# design.net
KiCad netlist of a schematic drawn in Altium Designer
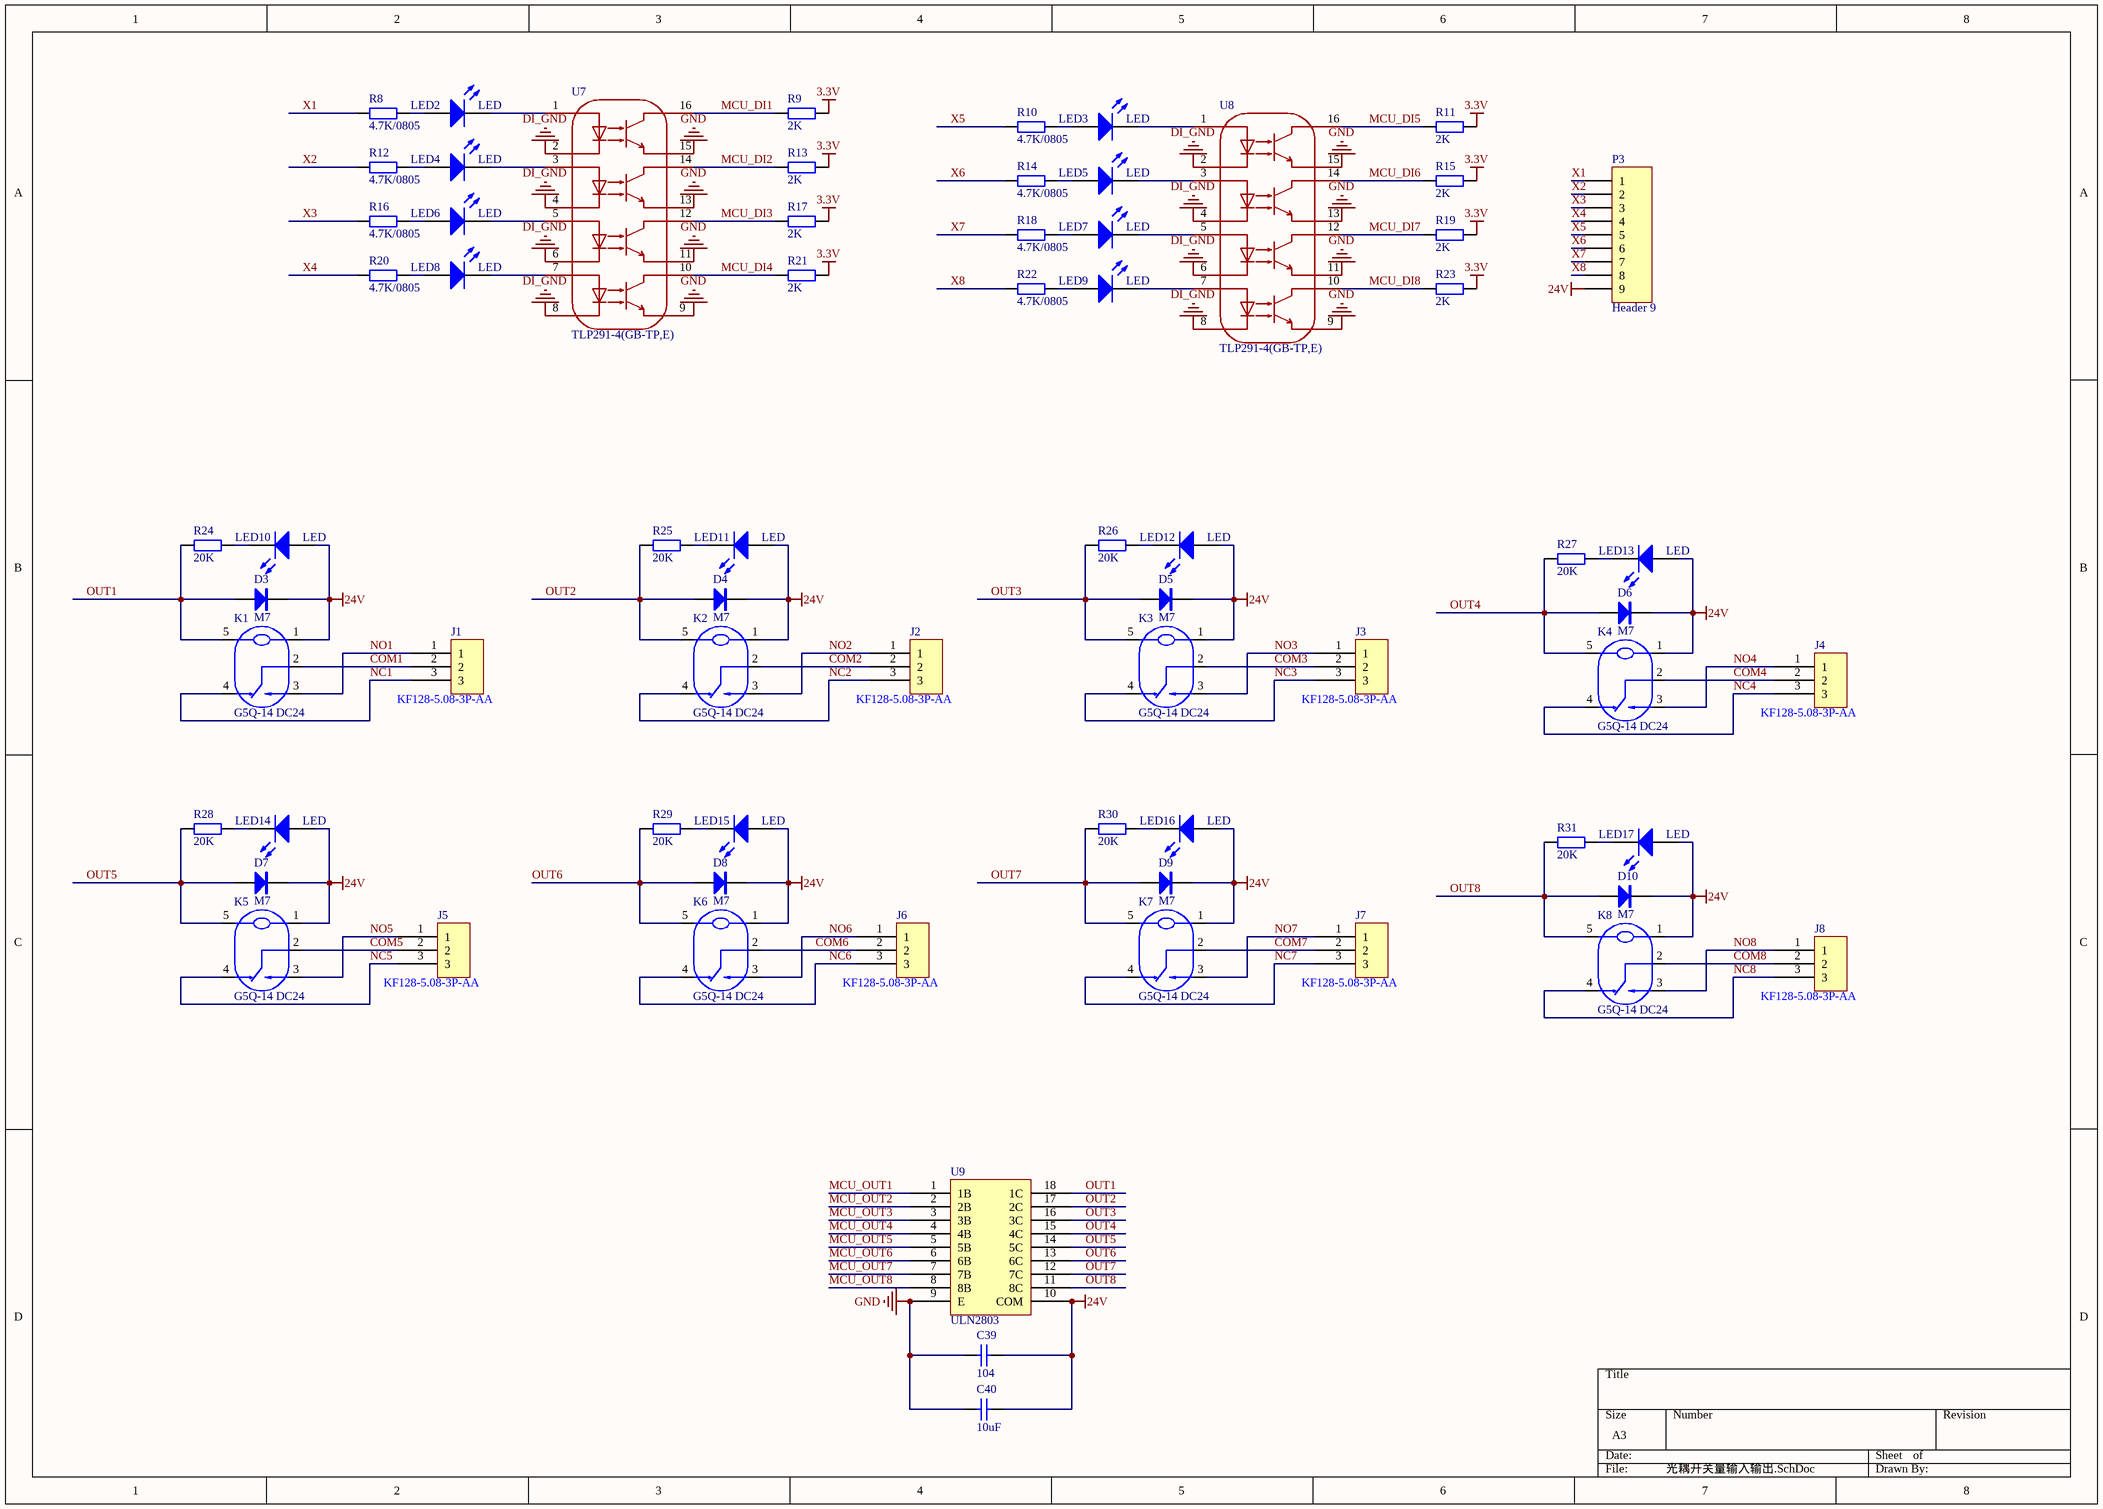
[diagram p0: 光耦开关量输入输出.SchDoc]

(export (version "E")
  (design (tool "Eeschema 10.0.6"))
  (components
    (comp (ref "C39")
      (value "104")
      (footprint "C 0603_L")
      (description "0603贴片电容")
      (fields (field (name "PUBLISHER") "Altium Limited"))
      (libsource (lib "STM32_PLC_20251215") (part "Cap"))
    )
    (comp (ref "C40")
      (value "10uF")
      (footprint "C 0603_L")
      (description "0603贴片电容")
      (fields (field (name "PUBLISHER") "Altium Limited"))
      (libsource (lib "STM32_PLC_20251215") (part "Cap"))
    )
    (comp (ref "D3")
      (value "M7")
      (footprint "SMA")
      (description "整流二极管")
      (libsource (lib "STM32_PLC_20251215") (part "M7"))
    )
    (comp (ref "D4")
      (value "M7")
      (footprint "SMA")
      (description "整流二极管")
      (libsource (lib "STM32_PLC_20251215") (part "M7"))
    )
    (comp (ref "D5")
      (value "M7")
      (footprint "SMA")
      (description "整流二极管")
      (libsource (lib "STM32_PLC_20251215") (part "M7"))
    )
    (comp (ref "D6")
      (value "M7")
      (footprint "SMA")
      (description "整流二极管")
      (libsource (lib "STM32_PLC_20251215") (part "M7"))
    )
    (comp (ref "D7")
      (value "M7")
      (footprint "SMA")
      (description "整流二极管")
      (libsource (lib "STM32_PLC_20251215") (part "M7"))
    )
    (comp (ref "D8")
      (value "M7")
      (footprint "SMA")
      (description "整流二极管")
      (libsource (lib "STM32_PLC_20251215") (part "M7"))
    )
    (comp (ref "D9")
      (value "M7")
      (footprint "SMA")
      (description "整流二极管")
      (libsource (lib "STM32_PLC_20251215") (part "M7"))
    )
    (comp (ref "D10")
      (value "M7")
      (footprint "SMA")
      (description "整流二极管")
      (libsource (lib "STM32_PLC_20251215") (part "M7"))
    )
    (comp (ref "J1")
      (value "KF128-5.08-3P-AA")
      (footprint "KF128-5.08-3P")
      (description "KF128-5.08-3P-AA端座")
      (fields (field (name "MANUFACTURER") "KEFA(科发)"))
      (libsource (lib "STM32_PLC_20251215") (part "KF128-5.08-3P-AA"))
    )
    (comp (ref "J2")
      (value "KF128-5.08-3P-AA")
      (footprint "KF128-5.08-3P")
      (description "KF128-5.08-3P-AA端座")
      (fields (field (name "MANUFACTURER") "KEFA(科发)"))
      (libsource (lib "STM32_PLC_20251215") (part "KF128-5.08-3P-AA"))
    )
    (comp (ref "J3")
      (value "KF128-5.08-3P-AA")
      (footprint "KF128-5.08-3P")
      (description "KF128-5.08-3P-AA端座")
      (fields (field (name "MANUFACTURER") "KEFA(科发)"))
      (libsource (lib "STM32_PLC_20251215") (part "KF128-5.08-3P-AA"))
    )
    (comp (ref "J4")
      (value "KF128-5.08-3P-AA")
      (footprint "KF128-5.08-3P")
      (description "KF128-5.08-3P-AA端座")
      (fields (field (name "MANUFACTURER") "KEFA(科发)"))
      (libsource (lib "STM32_PLC_20251215") (part "KF128-5.08-3P-AA"))
    )
    (comp (ref "J5")
      (value "KF128-5.08-3P-AA")
      (footprint "KF128-5.08-3P")
      (description "KF128-5.08-3P-AA端座")
      (fields (field (name "MANUFACTURER") "KEFA(科发)"))
      (libsource (lib "STM32_PLC_20251215") (part "KF128-5.08-3P-AA"))
    )
    (comp (ref "J6")
      (value "KF128-5.08-3P-AA")
      (footprint "KF128-5.08-3P")
      (description "KF128-5.08-3P-AA端座")
      (fields (field (name "MANUFACTURER") "KEFA(科发)"))
      (libsource (lib "STM32_PLC_20251215") (part "KF128-5.08-3P-AA"))
    )
    (comp (ref "J7")
      (value "KF128-5.08-3P-AA")
      (footprint "KF128-5.08-3P")
      (description "KF128-5.08-3P-AA端座")
      (fields (field (name "MANUFACTURER") "KEFA(科发)"))
      (libsource (lib "STM32_PLC_20251215") (part "KF128-5.08-3P-AA"))
    )
    (comp (ref "J8")
      (value "KF128-5.08-3P-AA")
      (footprint "KF128-5.08-3P")
      (description "KF128-5.08-3P-AA端座")
      (fields (field (name "MANUFACTURER") "KEFA(科发)"))
      (libsource (lib "STM32_PLC_20251215") (part "KF128-5.08-3P-AA"))
    )
    (comp (ref "K1")
      (value "G5Q-14 DC24")
      (footprint "RELAY-TH_G5Q-14-DCXX")
      (description "欧姆龙24V继电器，单刀双掷")
      (fields (field (name "MANUFACTURER") "OMRON(欧姆龙)"))
      (libsource (lib "STM32F407_PLC_20260104_") (part "G5Q-14 DC24"))
    )
    (comp (ref "K2")
      (value "G5Q-14 DC24")
      (footprint "RELAY-TH_G5Q-14-DCXX")
      (description "欧姆龙24V继电器，单刀双掷")
      (fields (field (name "MANUFACTURER") "OMRON(欧姆龙)"))
      (libsource (lib "STM32F407_PLC_20260104_") (part "G5Q-14 DC24"))
    )
    (comp (ref "K3")
      (value "G5Q-14 DC24")
      (footprint "RELAY-TH_G5Q-14-DCXX")
      (description "欧姆龙24V继电器，单刀双掷")
      (fields (field (name "MANUFACTURER") "OMRON(欧姆龙)"))
      (libsource (lib "STM32F407_PLC_20260104_") (part "G5Q-14 DC24"))
    )
    (comp (ref "K4")
      (value "G5Q-14 DC24")
      (footprint "RELAY-TH_G5Q-14-DCXX")
      (description "欧姆龙24V继电器，单刀双掷")
      (fields (field (name "MANUFACTURER") "OMRON(欧姆龙)"))
      (libsource (lib "STM32F407_PLC_20260104_") (part "G5Q-14 DC24"))
    )
    (comp (ref "K5")
      (value "G5Q-14 DC24")
      (footprint "RELAY-TH_G5Q-14-DCXX")
      (description "欧姆龙24V继电器，单刀双掷")
      (fields (field (name "MANUFACTURER") "OMRON(欧姆龙)"))
      (libsource (lib "STM32F407_PLC_20260104_") (part "G5Q-14 DC24"))
    )
    (comp (ref "K6")
      (value "G5Q-14 DC24")
      (footprint "RELAY-TH_G5Q-14-DCXX")
      (description "欧姆龙24V继电器，单刀双掷")
      (fields (field (name "MANUFACTURER") "OMRON(欧姆龙)"))
      (libsource (lib "STM32F407_PLC_20260104_") (part "G5Q-14 DC24"))
    )
    (comp (ref "K7")
      (value "G5Q-14 DC24")
      (footprint "RELAY-TH_G5Q-14-DCXX")
      (description "欧姆龙24V继电器，单刀双掷")
      (fields (field (name "MANUFACTURER") "OMRON(欧姆龙)"))
      (libsource (lib "STM32F407_PLC_20260104_") (part "G5Q-14 DC24"))
    )
    (comp (ref "K8")
      (value "G5Q-14 DC24")
      (footprint "RELAY-TH_G5Q-14-DCXX")
      (description "欧姆龙24V继电器，单刀双掷")
      (fields (field (name "MANUFACTURER") "OMRON(欧姆龙)"))
      (libsource (lib "STM32F407_PLC_20260104_") (part "G5Q-14 DC24"))
    )
    (comp (ref "LED2")
      (value "LED")
      (footprint "LED 0603R")
      (description "0603发光二极管")
      (fields (field (name "PUBLISHER") "Altium Limited"))
      (libsource (lib "STM32_PLC_20251215_1") (part "LED"))
    )
    (comp (ref "LED3")
      (value "LED")
      (footprint "LED 0603R")
      (description "0603发光二极管")
      (fields (field (name "PUBLISHER") "Altium Limited"))
      (libsource (lib "STM32_PLC_20251215_1") (part "LED"))
    )
    (comp (ref "LED4")
      (value "LED")
      (footprint "LED 0603R")
      (description "0603发光二极管")
      (fields (field (name "PUBLISHER") "Altium Limited"))
      (libsource (lib "STM32_PLC_20251215_1") (part "LED"))
    )
    (comp (ref "LED5")
      (value "LED")
      (footprint "LED 0603R")
      (description "0603发光二极管")
      (fields (field (name "PUBLISHER") "Altium Limited"))
      (libsource (lib "STM32_PLC_20251215_1") (part "LED"))
    )
    (comp (ref "LED6")
      (value "LED")
      (footprint "LED 0603R")
      (description "0603发光二极管")
      (fields (field (name "PUBLISHER") "Altium Limited"))
      (libsource (lib "STM32_PLC_20251215_1") (part "LED"))
    )
    (comp (ref "LED7")
      (value "LED")
      (footprint "LED 0603R")
      (description "0603发光二极管")
      (fields (field (name "PUBLISHER") "Altium Limited"))
      (libsource (lib "STM32_PLC_20251215_1") (part "LED"))
    )
    (comp (ref "LED8")
      (value "LED")
      (footprint "LED 0603R")
      (description "0603发光二极管")
      (fields (field (name "PUBLISHER") "Altium Limited"))
      (libsource (lib "STM32_PLC_20251215_1") (part "LED"))
    )
    (comp (ref "LED9")
      (value "LED")
      (footprint "LED 0603R")
      (description "0603发光二极管")
      (fields (field (name "PUBLISHER") "Altium Limited"))
      (libsource (lib "STM32_PLC_20251215_1") (part "LED"))
    )
    (comp (ref "LED10")
      (value "LED")
      (footprint "LED 0603R")
      (description "0603发光二极管")
      (fields (field (name "PUBLISHER") "Altium Limited"))
      (libsource (lib "STM32_PLC_20251215_1") (part "LED"))
    )
    (comp (ref "LED11")
      (value "LED")
      (footprint "LED 0603R")
      (description "0603发光二极管")
      (fields (field (name "PUBLISHER") "Altium Limited"))
      (libsource (lib "STM32_PLC_20251215_1") (part "LED"))
    )
    (comp (ref "LED12")
      (value "LED")
      (footprint "LED 0603R")
      (description "0603发光二极管")
      (fields (field (name "PUBLISHER") "Altium Limited"))
      (libsource (lib "STM32_PLC_20251215_1") (part "LED"))
    )
    (comp (ref "LED13")
      (value "LED")
      (footprint "LED 0603R")
      (description "0603发光二极管")
      (fields (field (name "PUBLISHER") "Altium Limited"))
      (libsource (lib "STM32_PLC_20251215_1") (part "LED"))
    )
    (comp (ref "LED14")
      (value "LED")
      (footprint "LED 0603R")
      (description "0603发光二极管")
      (fields (field (name "PUBLISHER") "Altium Limited"))
      (libsource (lib "STM32_PLC_20251215_1") (part "LED"))
    )
    (comp (ref "LED15")
      (value "LED")
      (footprint "LED 0603R")
      (description "0603发光二极管")
      (fields (field (name "PUBLISHER") "Altium Limited"))
      (libsource (lib "STM32_PLC_20251215_1") (part "LED"))
    )
    (comp (ref "LED16")
      (value "LED")
      (footprint "LED 0603R")
      (description "0603发光二极管")
      (fields (field (name "PUBLISHER") "Altium Limited"))
      (libsource (lib "STM32_PLC_20251215_1") (part "LED"))
    )
    (comp (ref "LED17")
      (value "LED")
      (footprint "LED 0603R")
      (description "0603发光二极管")
      (fields (field (name "PUBLISHER") "Altium Limited"))
      (libsource (lib "STM32_PLC_20251215_1") (part "LED"))
    )
    (comp (ref "P3")
      (value "Header 9")
      (footprint "KF128-5.08-9P")
      (description "Header, 9-Pin")
      (fields (field (name "PUBLISHER") "Altium Limited"))
      (libsource (lib "Miscellaneous Connectors") (part "Header 9"))
    )
    (comp (ref "R8")
      (value "4.7K/0805")
      (footprint "R0805_L")
      (description "R0805贴片电阻")
      (fields (field (name "版权归属") "源创客"))
      (libsource (lib "STM32_PLC_20251215_1") (part "Res_15"))
    )
    (comp (ref "R9")
      (value "2K")
      (footprint "R 0603_L")
      (description "0603贴片电阻")
      (fields (field (name "版权归属") "源创客"))
      (libsource (lib "STM32_PLC_20251215") (part "Res"))
    )
    (comp (ref "R10")
      (value "4.7K/0805")
      (footprint "R0805_L")
      (description "R0805贴片电阻")
      (fields (field (name "版权归属") "源创客"))
      (libsource (lib "STM32_PLC_20251215_1") (part "Res_15"))
    )
    (comp (ref "R11")
      (value "2K")
      (footprint "R 0603_L")
      (description "0603贴片电阻")
      (fields (field (name "版权归属") "源创客"))
      (libsource (lib "STM32_PLC_20251215") (part "Res"))
    )
    (comp (ref "R12")
      (value "4.7K/0805")
      (footprint "R0805_L")
      (description "R0805贴片电阻")
      (fields (field (name "版权归属") "源创客"))
      (libsource (lib "STM32_PLC_20251215_1") (part "Res_15"))
    )
    (comp (ref "R13")
      (value "2K")
      (footprint "R 0603_L")
      (description "0603贴片电阻")
      (fields (field (name "版权归属") "源创客"))
      (libsource (lib "STM32_PLC_20251215") (part "Res"))
    )
    (comp (ref "R14")
      (value "4.7K/0805")
      (footprint "R0805_L")
      (description "R0805贴片电阻")
      (fields (field (name "版权归属") "源创客"))
      (libsource (lib "STM32_PLC_20251215_1") (part "Res_15"))
    )
    (comp (ref "R15")
      (value "2K")
      (footprint "R 0603_L")
      (description "0603贴片电阻")
      (fields (field (name "版权归属") "源创客"))
      (libsource (lib "STM32_PLC_20251215") (part "Res"))
    )
    (comp (ref "R16")
      (value "4.7K/0805")
      (footprint "R0805_L")
      (description "R0805贴片电阻")
      (fields (field (name "版权归属") "源创客"))
      (libsource (lib "STM32_PLC_20251215_1") (part "Res_15"))
    )
    (comp (ref "R17")
      (value "2K")
      (footprint "R 0603_L")
      (description "0603贴片电阻")
      (fields (field (name "版权归属") "源创客"))
      (libsource (lib "STM32_PLC_20251215") (part "Res"))
    )
    (comp (ref "R18")
      (value "4.7K/0805")
      (footprint "R0805_L")
      (description "R0805贴片电阻")
      (fields (field (name "版权归属") "源创客"))
      (libsource (lib "STM32_PLC_20251215_1") (part "Res_15"))
    )
    (comp (ref "R19")
      (value "2K")
      (footprint "R 0603_L")
      (description "0603贴片电阻")
      (fields (field (name "版权归属") "源创客"))
      (libsource (lib "STM32_PLC_20251215") (part "Res"))
    )
    (comp (ref "R20")
      (value "4.7K/0805")
      (footprint "R0805_L")
      (description "R0805贴片电阻")
      (fields (field (name "版权归属") "源创客"))
      (libsource (lib "STM32_PLC_20251215_1") (part "Res_15"))
    )
    (comp (ref "R21")
      (value "2K")
      (footprint "R 0603_L")
      (description "0603贴片电阻")
      (fields (field (name "版权归属") "源创客"))
      (libsource (lib "STM32_PLC_20251215") (part "Res"))
    )
    (comp (ref "R22")
      (value "4.7K/0805")
      (footprint "R0805_L")
      (description "R0805贴片电阻")
      (fields (field (name "版权归属") "源创客"))
      (libsource (lib "STM32_PLC_20251215_1") (part "Res_15"))
    )
    (comp (ref "R23")
      (value "2K")
      (footprint "R 0603_L")
      (description "0603贴片电阻")
      (fields (field (name "版权归属") "源创客"))
      (libsource (lib "STM32_PLC_20251215") (part "Res"))
    )
    (comp (ref "R24")
      (value "20K")
      (footprint "R 0603_L")
      (description "0603贴片电阻")
      (fields (field (name "版权归属") "源创客"))
      (libsource (lib "STM32_PLC_20251215") (part "Res"))
    )
    (comp (ref "R25")
      (value "20K")
      (footprint "R 0603_L")
      (description "0603贴片电阻")
      (fields (field (name "版权归属") "源创客"))
      (libsource (lib "STM32_PLC_20251215") (part "Res"))
    )
    (comp (ref "R26")
      (value "20K")
      (footprint "R 0603_L")
      (description "0603贴片电阻")
      (fields (field (name "版权归属") "源创客"))
      (libsource (lib "STM32_PLC_20251215") (part "Res"))
    )
    (comp (ref "R27")
      (value "20K")
      (footprint "R 0603_L")
      (description "0603贴片电阻")
      (fields (field (name "版权归属") "源创客"))
      (libsource (lib "STM32_PLC_20251215") (part "Res"))
    )
    (comp (ref "R28")
      (value "20K")
      (footprint "R 0603_L")
      (description "0603贴片电阻")
      (fields (field (name "版权归属") "源创客"))
      (libsource (lib "STM32_PLC_20251215") (part "Res"))
    )
    (comp (ref "R29")
      (value "20K")
      (footprint "R 0603_L")
      (description "0603贴片电阻")
      (fields (field (name "版权归属") "源创客"))
      (libsource (lib "STM32_PLC_20251215") (part "Res"))
    )
    (comp (ref "R30")
      (value "20K")
      (footprint "R 0603_L")
      (description "0603贴片电阻")
      (fields (field (name "版权归属") "源创客"))
      (libsource (lib "STM32_PLC_20251215") (part "Res"))
    )
    (comp (ref "R31")
      (value "20K")
      (footprint "R 0603_L")
      (description "0603贴片电阻")
      (fields (field (name "版权归属") "源创客"))
      (libsource (lib "STM32_PLC_20251215") (part "Res"))
    )
    (comp (ref "U7")
      (value "TLP291-4(GB-TP,E)")
      (footprint "SOP-16_L10.3-W4.4-P1.27-LS7.0-BL")
      (description "光耦")
      (fields (field (name "MANUFACTURER") "TOSHIBA(东芝)"))
      (libsource (lib "STM32F407_PLC_20260104_") (part "TLP291-4(GB-TP,E)"))
    )
    (comp (ref "U8")
      (value "TLP291-4(GB-TP,E)")
      (footprint "SOP-16_L10.3-W4.4-P1.27-LS7.0-BL")
      (description "光耦")
      (fields (field (name "MANUFACTURER") "TOSHIBA(东芝)"))
      (libsource (lib "STM32F407_PLC_20260104_") (part "TLP291-4(GB-TP,E)"))
    )
    (comp (ref "U9")
      (value "ULN2803")
      (footprint "SOP-18_L11.6-W7.5-P1.27-LS10.3-BL")
      (description "达林顿驱动")
      (fields (field (name "MANUFACTURER") "Siproin(上海矽朋)"))
      (libsource (lib "STM32F407_PLC_20260104_") (part "ULN2803"))
    )
  )
  (nets
    (net (code "1") (name "/COM1") (class "Default")
      (node (ref "J1") (pin "2") (pinfunction "2_2") (pintype "passive"))
      (node (ref "K1") (pin "2") (pinfunction "2_2") (pintype "passive"))
    )
    (net (code "2") (name "/COM2") (class "Default")
      (node (ref "J2") (pin "2") (pinfunction "2_2") (pintype "passive"))
      (node (ref "K2") (pin "2") (pinfunction "2_2") (pintype "passive"))
    )
    (net (code "3") (name "/COM3") (class "Default")
      (node (ref "J3") (pin "2") (pinfunction "2_2") (pintype "passive"))
      (node (ref "K3") (pin "2") (pinfunction "2_2") (pintype "passive"))
    )
    (net (code "4") (name "/COM4") (class "Default")
      (node (ref "J4") (pin "2") (pinfunction "2_2") (pintype "passive"))
      (node (ref "K4") (pin "2") (pinfunction "2_2") (pintype "passive"))
    )
    (net (code "5") (name "/COM5") (class "Default")
      (node (ref "J5") (pin "2") (pinfunction "2_2") (pintype "passive"))
      (node (ref "K5") (pin "2") (pinfunction "2_2") (pintype "passive"))
    )
    (net (code "6") (name "/COM6") (class "Default")
      (node (ref "J6") (pin "2") (pinfunction "2_2") (pintype "passive"))
      (node (ref "K6") (pin "2") (pinfunction "2_2") (pintype "passive"))
    )
    (net (code "7") (name "/COM7") (class "Default")
      (node (ref "J7") (pin "2") (pinfunction "2_2") (pintype "passive"))
      (node (ref "K7") (pin "2") (pinfunction "2_2") (pintype "passive"))
    )
    (net (code "8") (name "/COM8") (class "Default")
      (node (ref "J8") (pin "2") (pinfunction "2_2") (pintype "passive"))
      (node (ref "K8") (pin "2") (pinfunction "2_2") (pintype "passive"))
    )
    (net (code "9") (name "/MCU_DI1") (class "Default")
      (node (ref "R9") (pin "2") (pinfunction "2_2") (pintype "passive"))
      (node (ref "U7") (pin "16") (pinfunction "16_16") (pintype "passive"))
    )
    (net (code "10") (name "/MCU_DI2") (class "Default")
      (node (ref "R13") (pin "2") (pinfunction "2_2") (pintype "passive"))
      (node (ref "U7") (pin "14") (pinfunction "14_14") (pintype "passive"))
    )
    (net (code "11") (name "/MCU_DI3") (class "Default")
      (node (ref "R17") (pin "2") (pinfunction "2_2") (pintype "passive"))
      (node (ref "U7") (pin "12") (pinfunction "12_12") (pintype "passive"))
    )
    (net (code "12") (name "/MCU_DI4") (class "Default")
      (node (ref "R21") (pin "2") (pinfunction "2_2") (pintype "passive"))
      (node (ref "U7") (pin "10") (pinfunction "10_10") (pintype "passive"))
    )
    (net (code "13") (name "/MCU_DI5") (class "Default")
      (node (ref "R11") (pin "2") (pinfunction "2_2") (pintype "passive"))
      (node (ref "U8") (pin "16") (pinfunction "16_16") (pintype "passive"))
    )
    (net (code "14") (name "/MCU_DI6") (class "Default")
      (node (ref "R15") (pin "2") (pinfunction "2_2") (pintype "passive"))
      (node (ref "U8") (pin "14") (pinfunction "14_14") (pintype "passive"))
    )
    (net (code "15") (name "/MCU_DI7") (class "Default")
      (node (ref "R19") (pin "2") (pinfunction "2_2") (pintype "passive"))
      (node (ref "U8") (pin "12") (pinfunction "12_12") (pintype "passive"))
    )
    (net (code "16") (name "/MCU_DI8") (class "Default")
      (node (ref "R23") (pin "2") (pinfunction "2_2") (pintype "passive"))
      (node (ref "U8") (pin "10") (pinfunction "10_10") (pintype "passive"))
    )
    (net (code "17") (name "/MCU_OUT1") (class "Default")
      (node (ref "U9") (pin "1") (pinfunction "1B_1") (pintype "passive"))
    )
    (net (code "18") (name "/MCU_OUT2") (class "Default")
      (node (ref "U9") (pin "2") (pinfunction "2B_2") (pintype "passive"))
    )
    (net (code "19") (name "/MCU_OUT3") (class "Default")
      (node (ref "U9") (pin "3") (pinfunction "3B_3") (pintype "passive"))
    )
    (net (code "20") (name "/MCU_OUT4") (class "Default")
      (node (ref "U9") (pin "4") (pinfunction "4B_4") (pintype "passive"))
    )
    (net (code "21") (name "/MCU_OUT5") (class "Default")
      (node (ref "U9") (pin "5") (pinfunction "5B_5") (pintype "passive"))
    )
    (net (code "22") (name "/MCU_OUT6") (class "Default")
      (node (ref "U9") (pin "6") (pinfunction "6B_6") (pintype "passive"))
    )
    (net (code "23") (name "/MCU_OUT7") (class "Default")
      (node (ref "U9") (pin "7") (pinfunction "7B_7") (pintype "passive"))
    )
    (net (code "24") (name "/MCU_OUT8") (class "Default")
      (node (ref "U9") (pin "8") (pinfunction "8B_8") (pintype "passive"))
    )
    (net (code "25") (name "/NC1") (class "Default")
      (node (ref "J1") (pin "3") (pinfunction "3_3") (pintype "passive"))
      (node (ref "K1") (pin "4") (pinfunction "4_4") (pintype "passive"))
    )
    (net (code "26") (name "/NC2") (class "Default")
      (node (ref "J2") (pin "3") (pinfunction "3_3") (pintype "passive"))
      (node (ref "K2") (pin "4") (pinfunction "4_4") (pintype "passive"))
    )
    (net (code "27") (name "/NC3") (class "Default")
      (node (ref "J3") (pin "3") (pinfunction "3_3") (pintype "passive"))
      (node (ref "K3") (pin "4") (pinfunction "4_4") (pintype "passive"))
    )
    (net (code "28") (name "/NC4") (class "Default")
      (node (ref "J4") (pin "3") (pinfunction "3_3") (pintype "passive"))
      (node (ref "K4") (pin "4") (pinfunction "4_4") (pintype "passive"))
    )
    (net (code "29") (name "/NC5") (class "Default")
      (node (ref "J5") (pin "3") (pinfunction "3_3") (pintype "passive"))
      (node (ref "K5") (pin "4") (pinfunction "4_4") (pintype "passive"))
    )
    (net (code "30") (name "/NC6") (class "Default")
      (node (ref "J6") (pin "3") (pinfunction "3_3") (pintype "passive"))
      (node (ref "K6") (pin "4") (pinfunction "4_4") (pintype "passive"))
    )
    (net (code "31") (name "/NC7") (class "Default")
      (node (ref "J7") (pin "3") (pinfunction "3_3") (pintype "passive"))
      (node (ref "K7") (pin "4") (pinfunction "4_4") (pintype "passive"))
    )
    (net (code "32") (name "/NC8") (class "Default")
      (node (ref "J8") (pin "3") (pinfunction "3_3") (pintype "passive"))
      (node (ref "K8") (pin "4") (pinfunction "4_4") (pintype "passive"))
    )
    (net (code "33") (name "/NO1") (class "Default")
      (node (ref "J1") (pin "1") (pinfunction "1_1") (pintype "passive"))
      (node (ref "K1") (pin "3") (pinfunction "3_3") (pintype "passive"))
    )
    (net (code "34") (name "/NO2") (class "Default")
      (node (ref "J2") (pin "1") (pinfunction "1_1") (pintype "passive"))
      (node (ref "K2") (pin "3") (pinfunction "3_3") (pintype "passive"))
    )
    (net (code "35") (name "/NO3") (class "Default")
      (node (ref "J3") (pin "1") (pinfunction "1_1") (pintype "passive"))
      (node (ref "K3") (pin "3") (pinfunction "3_3") (pintype "passive"))
    )
    (net (code "36") (name "/NO4") (class "Default")
      (node (ref "J4") (pin "1") (pinfunction "1_1") (pintype "passive"))
      (node (ref "K4") (pin "3") (pinfunction "3_3") (pintype "passive"))
    )
    (net (code "37") (name "/NO5") (class "Default")
      (node (ref "J5") (pin "1") (pinfunction "1_1") (pintype "passive"))
      (node (ref "K5") (pin "3") (pinfunction "3_3") (pintype "passive"))
    )
    (net (code "38") (name "/NO6") (class "Default")
      (node (ref "J6") (pin "1") (pinfunction "1_1") (pintype "passive"))
      (node (ref "K6") (pin "3") (pinfunction "3_3") (pintype "passive"))
    )
    (net (code "39") (name "/NO7") (class "Default")
      (node (ref "J7") (pin "1") (pinfunction "1_1") (pintype "passive"))
      (node (ref "K7") (pin "3") (pinfunction "3_3") (pintype "passive"))
    )
    (net (code "40") (name "/NO8") (class "Default")
      (node (ref "J8") (pin "1") (pinfunction "1_1") (pintype "passive"))
      (node (ref "K8") (pin "3") (pinfunction "3_3") (pintype "passive"))
    )
    (net (code "41") (name "/OUT1") (class "Default")
      (node (ref "D3") (pin "1") (pinfunction "A_1") (pintype "passive"))
      (node (ref "K1") (pin "5") (pinfunction "5_5") (pintype "passive"))
      (node (ref "R24") (pin "2") (pinfunction "2_2") (pintype "passive"))
      (node (ref "U9") (pin "18") (pinfunction "1C_18") (pintype "passive"))
    )
    (net (code "42") (name "/OUT2") (class "Default")
      (node (ref "D4") (pin "1") (pinfunction "A_1") (pintype "passive"))
      (node (ref "K2") (pin "5") (pinfunction "5_5") (pintype "passive"))
      (node (ref "R25") (pin "2") (pinfunction "2_2") (pintype "passive"))
      (node (ref "U9") (pin "17") (pinfunction "2C_17") (pintype "passive"))
    )
    (net (code "43") (name "/OUT3") (class "Default")
      (node (ref "D5") (pin "1") (pinfunction "A_1") (pintype "passive"))
      (node (ref "K3") (pin "5") (pinfunction "5_5") (pintype "passive"))
      (node (ref "R26") (pin "2") (pinfunction "2_2") (pintype "passive"))
      (node (ref "U9") (pin "16") (pinfunction "3C_16") (pintype "passive"))
    )
    (net (code "44") (name "/OUT4") (class "Default")
      (node (ref "D6") (pin "1") (pinfunction "A_1") (pintype "passive"))
      (node (ref "K4") (pin "5") (pinfunction "5_5") (pintype "passive"))
      (node (ref "R27") (pin "2") (pinfunction "2_2") (pintype "passive"))
      (node (ref "U9") (pin "15") (pinfunction "4C_15") (pintype "passive"))
    )
    (net (code "45") (name "/OUT5") (class "Default")
      (node (ref "D7") (pin "1") (pinfunction "A_1") (pintype "passive"))
      (node (ref "K5") (pin "5") (pinfunction "5_5") (pintype "passive"))
      (node (ref "R28") (pin "2") (pinfunction "2_2") (pintype "passive"))
      (node (ref "U9") (pin "14") (pinfunction "5C_14") (pintype "passive"))
    )
    (net (code "46") (name "/OUT6") (class "Default")
      (node (ref "D8") (pin "1") (pinfunction "A_1") (pintype "passive"))
      (node (ref "K6") (pin "5") (pinfunction "5_5") (pintype "passive"))
      (node (ref "R29") (pin "2") (pinfunction "2_2") (pintype "passive"))
      (node (ref "U9") (pin "13") (pinfunction "6C_13") (pintype "passive"))
    )
    (net (code "47") (name "/OUT7") (class "Default")
      (node (ref "D9") (pin "1") (pinfunction "A_1") (pintype "passive"))
      (node (ref "K7") (pin "5") (pinfunction "5_5") (pintype "passive"))
      (node (ref "R30") (pin "2") (pinfunction "2_2") (pintype "passive"))
      (node (ref "U9") (pin "12") (pinfunction "7C_12") (pintype "passive"))
    )
    (net (code "48") (name "/OUT8") (class "Default")
      (node (ref "D10") (pin "1") (pinfunction "A_1") (pintype "passive"))
      (node (ref "K8") (pin "5") (pinfunction "5_5") (pintype "passive"))
      (node (ref "R31") (pin "2") (pinfunction "2_2") (pintype "passive"))
      (node (ref "U9") (pin "11") (pinfunction "8C_11") (pintype "passive"))
    )
    (net (code "49") (name "/X1") (class "Default")
      (node (ref "P3") (pin "1") (pinfunction "1_1") (pintype "passive"))
      (node (ref "R8") (pin "1") (pinfunction "1_1") (pintype "passive"))
    )
    (net (code "50") (name "/X2") (class "Default")
      (node (ref "P3") (pin "2") (pinfunction "2_2") (pintype "passive"))
      (node (ref "R12") (pin "1") (pinfunction "1_1") (pintype "passive"))
    )
    (net (code "51") (name "/X3") (class "Default")
      (node (ref "P3") (pin "3") (pinfunction "3_3") (pintype "passive"))
      (node (ref "R16") (pin "1") (pinfunction "1_1") (pintype "passive"))
    )
    (net (code "52") (name "/X4") (class "Default")
      (node (ref "P3") (pin "4") (pinfunction "4_4") (pintype "passive"))
      (node (ref "R20") (pin "1") (pinfunction "1_1") (pintype "passive"))
    )
    (net (code "53") (name "/X5") (class "Default")
      (node (ref "P3") (pin "5") (pinfunction "5_5") (pintype "passive"))
      (node (ref "R10") (pin "1") (pinfunction "1_1") (pintype "passive"))
    )
    (net (code "54") (name "/X6") (class "Default")
      (node (ref "P3") (pin "6") (pinfunction "6_6") (pintype "passive"))
      (node (ref "R14") (pin "1") (pinfunction "1_1") (pintype "passive"))
    )
    (net (code "55") (name "/X7") (class "Default")
      (node (ref "P3") (pin "7") (pinfunction "7_7") (pintype "passive"))
      (node (ref "R18") (pin "1") (pinfunction "1_1") (pintype "passive"))
    )
    (net (code "56") (name "/X8") (class "Default")
      (node (ref "P3") (pin "8") (pinfunction "8_8") (pintype "passive"))
      (node (ref "R22") (pin "1") (pinfunction "1_1") (pintype "passive"))
    )
    (net (code "57") (name "3.3V") (class "Default")
      (node (ref "R11") (pin "1") (pinfunction "1_1") (pintype "passive"))
      (node (ref "R13") (pin "1") (pinfunction "1_1") (pintype "passive"))
      (node (ref "R15") (pin "1") (pinfunction "1_1") (pintype "passive"))
      (node (ref "R17") (pin "1") (pinfunction "1_1") (pintype "passive"))
      (node (ref "R19") (pin "1") (pinfunction "1_1") (pintype "passive"))
      (node (ref "R21") (pin "1") (pinfunction "1_1") (pintype "passive"))
      (node (ref "R23") (pin "1") (pinfunction "1_1") (pintype "passive"))
      (node (ref "R9") (pin "1") (pinfunction "1_1") (pintype "passive"))
    )
    (net (code "58") (name "24V") (class "Default")
      (node (ref "C39") (pin "1") (pinfunction "1_1") (pintype "passive"))
      (node (ref "C40") (pin "1") (pinfunction "1_1") (pintype "passive"))
      (node (ref "D10") (pin "2") (pinfunction "K_2") (pintype "passive"))
      (node (ref "D3") (pin "2") (pinfunction "K_2") (pintype "passive"))
      (node (ref "D4") (pin "2") (pinfunction "K_2") (pintype "passive"))
      (node (ref "D5") (pin "2") (pinfunction "K_2") (pintype "passive"))
      (node (ref "D6") (pin "2") (pinfunction "K_2") (pintype "passive"))
      (node (ref "D7") (pin "2") (pinfunction "K_2") (pintype "passive"))
      (node (ref "D8") (pin "2") (pinfunction "K_2") (pintype "passive"))
      (node (ref "D9") (pin "2") (pinfunction "K_2") (pintype "passive"))
      (node (ref "K1") (pin "1") (pinfunction "1_1") (pintype "passive"))
      (node (ref "K2") (pin "1") (pinfunction "1_1") (pintype "passive"))
      (node (ref "K3") (pin "1") (pinfunction "1_1") (pintype "passive"))
      (node (ref "K4") (pin "1") (pinfunction "1_1") (pintype "passive"))
      (node (ref "K5") (pin "1") (pinfunction "1_1") (pintype "passive"))
      (node (ref "K6") (pin "1") (pinfunction "1_1") (pintype "passive"))
      (node (ref "K7") (pin "1") (pinfunction "1_1") (pintype "passive"))
      (node (ref "K8") (pin "1") (pinfunction "1_1") (pintype "passive"))
      (node (ref "LED10") (pin "1") (pinfunction "A_1") (pintype "passive"))
      (node (ref "LED11") (pin "1") (pinfunction "A_1") (pintype "passive"))
      (node (ref "LED12") (pin "1") (pinfunction "A_1") (pintype "passive"))
      (node (ref "LED13") (pin "1") (pinfunction "A_1") (pintype "passive"))
      (node (ref "LED14") (pin "1") (pinfunction "A_1") (pintype "passive"))
      (node (ref "LED15") (pin "1") (pinfunction "A_1") (pintype "passive"))
      (node (ref "LED16") (pin "1") (pinfunction "A_1") (pintype "passive"))
      (node (ref "LED17") (pin "1") (pinfunction "A_1") (pintype "passive"))
      (node (ref "P3") (pin "9") (pinfunction "9_9") (pintype "passive"))
      (node (ref "U9") (pin "10") (pinfunction "COM_10") (pintype "passive"))
    )
    (net (code "59") (name "DI_GND") (class "Default")
      (node (ref "U7") (pin "2") (pinfunction "2_2") (pintype "passive"))
      (node (ref "U7") (pin "4") (pinfunction "4_4") (pintype "passive"))
      (node (ref "U7") (pin "6") (pinfunction "6_6") (pintype "passive"))
      (node (ref "U7") (pin "8") (pinfunction "8_8") (pintype "passive"))
      (node (ref "U8") (pin "2") (pinfunction "2_2") (pintype "passive"))
      (node (ref "U8") (pin "4") (pinfunction "4_4") (pintype "passive"))
      (node (ref "U8") (pin "6") (pinfunction "6_6") (pintype "passive"))
      (node (ref "U8") (pin "8") (pinfunction "8_8") (pintype "passive"))
    )
    (net (code "60") (name "GND") (class "Default")
      (node (ref "C39") (pin "2") (pinfunction "2_2") (pintype "passive"))
      (node (ref "C40") (pin "2") (pinfunction "2_2") (pintype "passive"))
      (node (ref "U7") (pin "11") (pinfunction "11_11") (pintype "passive"))
      (node (ref "U7") (pin "13") (pinfunction "13_13") (pintype "passive"))
      (node (ref "U7") (pin "15") (pinfunction "15_15") (pintype "passive"))
      (node (ref "U7") (pin "9") (pinfunction "9_9") (pintype "passive"))
      (node (ref "U8") (pin "11") (pinfunction "11_11") (pintype "passive"))
      (node (ref "U8") (pin "13") (pinfunction "13_13") (pintype "passive"))
      (node (ref "U8") (pin "15") (pinfunction "15_15") (pintype "passive"))
      (node (ref "U8") (pin "9") (pinfunction "9_9") (pintype "passive"))
      (node (ref "U9") (pin "9") (pinfunction "E_9") (pintype "passive"))
    )
    (net (code "61") (name "Net-(LED2-A)") (class "Default")
      (node (ref "LED2") (pin "1") (pinfunction "A_1") (pintype "passive"))
      (node (ref "R8") (pin "2") (pinfunction "2_2") (pintype "passive"))
    )
    (net (code "62") (name "Net-(LED2-K)") (class "Default")
      (node (ref "LED2") (pin "2") (pinfunction "K_2") (pintype "passive"))
      (node (ref "U7") (pin "1") (pinfunction "1_1") (pintype "passive"))
    )
    (net (code "63") (name "Net-(LED3-A)") (class "Default")
      (node (ref "LED3") (pin "1") (pinfunction "A_1") (pintype "passive"))
      (node (ref "R10") (pin "2") (pinfunction "2_2") (pintype "passive"))
    )
    (net (code "64") (name "Net-(LED3-K)") (class "Default")
      (node (ref "LED3") (pin "2") (pinfunction "K_2") (pintype "passive"))
      (node (ref "U8") (pin "1") (pinfunction "1_1") (pintype "passive"))
    )
    (net (code "65") (name "Net-(LED4-A)") (class "Default")
      (node (ref "LED4") (pin "1") (pinfunction "A_1") (pintype "passive"))
      (node (ref "R12") (pin "2") (pinfunction "2_2") (pintype "passive"))
    )
    (net (code "66") (name "Net-(LED4-K)") (class "Default")
      (node (ref "LED4") (pin "2") (pinfunction "K_2") (pintype "passive"))
      (node (ref "U7") (pin "3") (pinfunction "3_3") (pintype "passive"))
    )
    (net (code "67") (name "Net-(LED5-A)") (class "Default")
      (node (ref "LED5") (pin "1") (pinfunction "A_1") (pintype "passive"))
      (node (ref "R14") (pin "2") (pinfunction "2_2") (pintype "passive"))
    )
    (net (code "68") (name "Net-(LED5-K)") (class "Default")
      (node (ref "LED5") (pin "2") (pinfunction "K_2") (pintype "passive"))
      (node (ref "U8") (pin "3") (pinfunction "3_3") (pintype "passive"))
    )
    (net (code "69") (name "Net-(LED6-A)") (class "Default")
      (node (ref "LED6") (pin "1") (pinfunction "A_1") (pintype "passive"))
      (node (ref "R16") (pin "2") (pinfunction "2_2") (pintype "passive"))
    )
    (net (code "70") (name "Net-(LED6-K)") (class "Default")
      (node (ref "LED6") (pin "2") (pinfunction "K_2") (pintype "passive"))
      (node (ref "U7") (pin "5") (pinfunction "5_5") (pintype "passive"))
    )
    (net (code "71") (name "Net-(LED7-A)") (class "Default")
      (node (ref "LED7") (pin "1") (pinfunction "A_1") (pintype "passive"))
      (node (ref "R18") (pin "2") (pinfunction "2_2") (pintype "passive"))
    )
    (net (code "72") (name "Net-(LED7-K)") (class "Default")
      (node (ref "LED7") (pin "2") (pinfunction "K_2") (pintype "passive"))
      (node (ref "U8") (pin "5") (pinfunction "5_5") (pintype "passive"))
    )
    (net (code "73") (name "Net-(LED8-A)") (class "Default")
      (node (ref "LED8") (pin "1") (pinfunction "A_1") (pintype "passive"))
      (node (ref "R20") (pin "2") (pinfunction "2_2") (pintype "passive"))
    )
    (net (code "74") (name "Net-(LED8-K)") (class "Default")
      (node (ref "LED8") (pin "2") (pinfunction "K_2") (pintype "passive"))
      (node (ref "U7") (pin "7") (pinfunction "7_7") (pintype "passive"))
    )
    (net (code "75") (name "Net-(LED9-A)") (class "Default")
      (node (ref "LED9") (pin "1") (pinfunction "A_1") (pintype "passive"))
      (node (ref "R22") (pin "2") (pinfunction "2_2") (pintype "passive"))
    )
    (net (code "76") (name "Net-(LED9-K)") (class "Default")
      (node (ref "LED9") (pin "2") (pinfunction "K_2") (pintype "passive"))
      (node (ref "U8") (pin "7") (pinfunction "7_7") (pintype "passive"))
    )
    (net (code "77") (name "Net-(LED10-K)") (class "Default")
      (node (ref "LED10") (pin "2") (pinfunction "K_2") (pintype "passive"))
      (node (ref "R24") (pin "1") (pinfunction "1_1") (pintype "passive"))
    )
    (net (code "78") (name "Net-(LED11-K)") (class "Default")
      (node (ref "LED11") (pin "2") (pinfunction "K_2") (pintype "passive"))
      (node (ref "R25") (pin "1") (pinfunction "1_1") (pintype "passive"))
    )
    (net (code "79") (name "Net-(LED12-K)") (class "Default")
      (node (ref "LED12") (pin "2") (pinfunction "K_2") (pintype "passive"))
      (node (ref "R26") (pin "1") (pinfunction "1_1") (pintype "passive"))
    )
    (net (code "80") (name "Net-(LED13-K)") (class "Default")
      (node (ref "LED13") (pin "2") (pinfunction "K_2") (pintype "passive"))
      (node (ref "R27") (pin "1") (pinfunction "1_1") (pintype "passive"))
    )
    (net (code "81") (name "Net-(LED14-K)") (class "Default")
      (node (ref "LED14") (pin "2") (pinfunction "K_2") (pintype "passive"))
      (node (ref "R28") (pin "1") (pinfunction "1_1") (pintype "passive"))
    )
    (net (code "82") (name "Net-(LED15-K)") (class "Default")
      (node (ref "LED15") (pin "2") (pinfunction "K_2") (pintype "passive"))
      (node (ref "R29") (pin "1") (pinfunction "1_1") (pintype "passive"))
    )
    (net (code "83") (name "Net-(LED16-K)") (class "Default")
      (node (ref "LED16") (pin "2") (pinfunction "K_2") (pintype "passive"))
      (node (ref "R30") (pin "1") (pinfunction "1_1") (pintype "passive"))
    )
    (net (code "84") (name "Net-(LED17-K)") (class "Default")
      (node (ref "LED17") (pin "2") (pinfunction "K_2") (pintype "passive"))
      (node (ref "R31") (pin "1") (pinfunction "1_1") (pintype "passive"))
    )
  )
)
